# ram.net
KiCad netlist of a schematic drawn in EAGLE
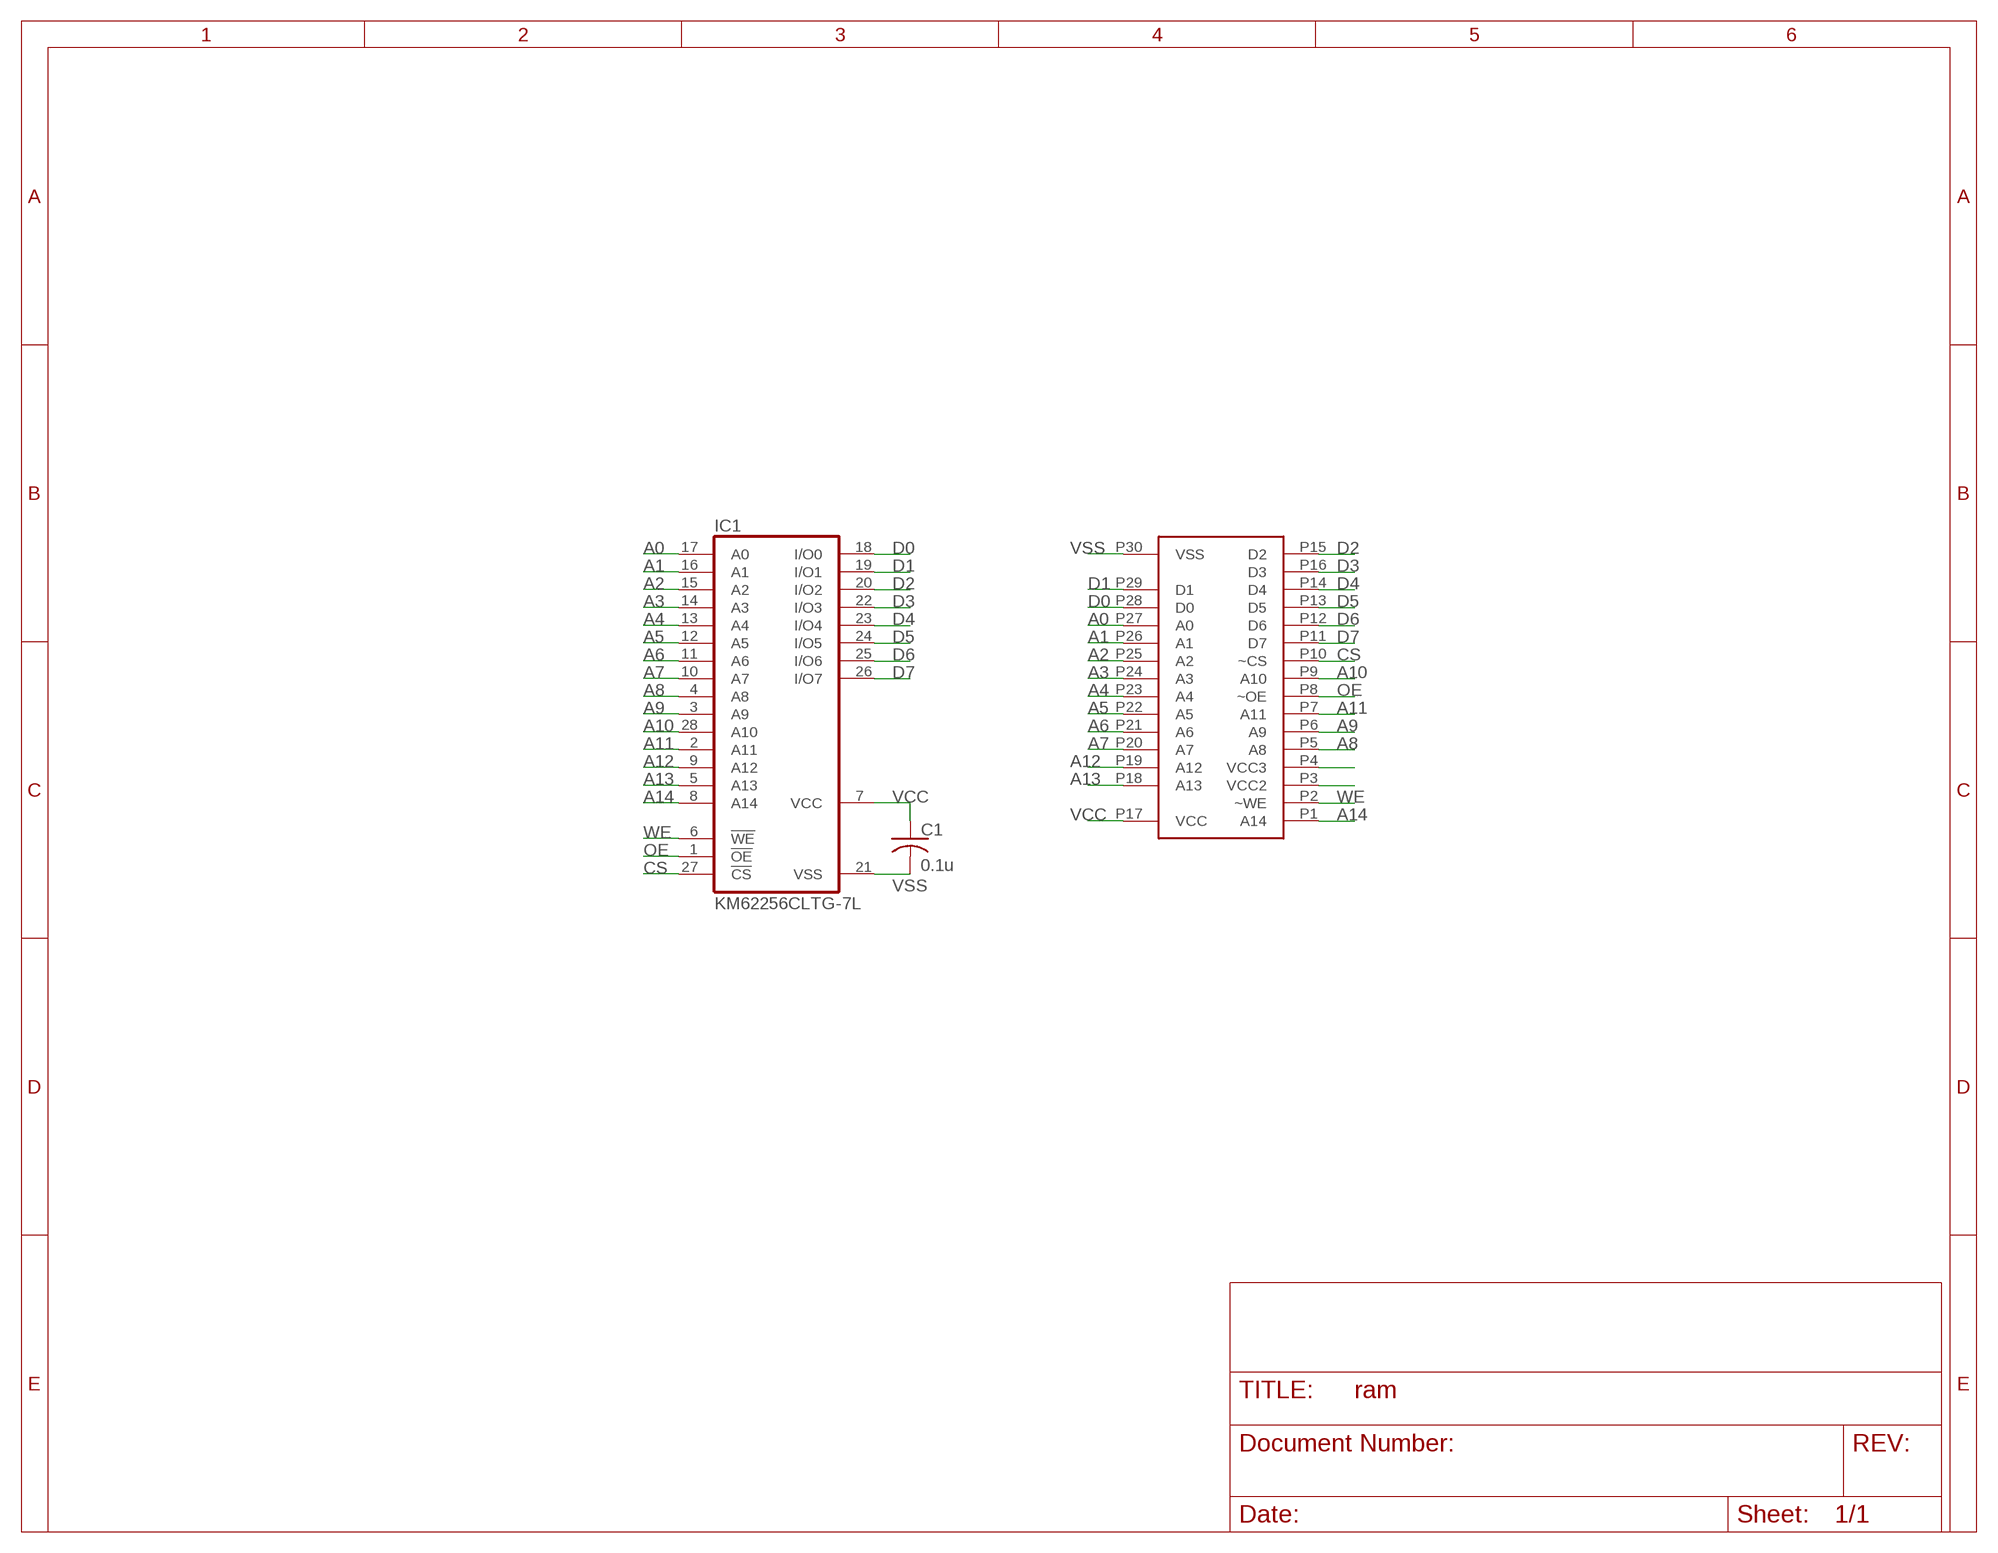
[diagram p0: schematic, sheet 1]

(export (version "E")
  (design (tool "Eeschema 10.0.6"))
  (components
    (comp (ref "C1")
      (value "0.1u")
      (footprint "eagle-import:C0603")
      (libsource (lib "eagle-import") (part "C-USC0603"))
    )
    (comp (ref "IC1")
      (value "KM62256CLTG-7L")
      (footprint "eagle-import:TSOP1-28")
      (libsource (lib "eagle-import") (part "KM62256C_TSOP28FLTG-7L"))
    )
    (comp (ref "U$1")
      (value "RAMPORT")
      (footprint "eagle-import:CASIORAM")
      (libsource (lib "eagle-import") (part "RAMPORT"))
    )
  )
  (nets
    (net (code "1") (name "/A0") (class "Default")
      (node (ref "IC1") (pin "17") (pinfunction "A0_17") (pintype "input"))
      (node (ref "U$1") (pin "P27") (pinfunction "A0_P27") (pintype "bidirectional"))
    )
    (net (code "2") (name "/A1") (class "Default")
      (node (ref "IC1") (pin "16") (pinfunction "A1_16") (pintype "input"))
      (node (ref "U$1") (pin "P26") (pinfunction "A1_P26") (pintype "bidirectional"))
    )
    (net (code "3") (name "/A2") (class "Default")
      (node (ref "IC1") (pin "15") (pinfunction "A2_15") (pintype "input"))
      (node (ref "U$1") (pin "P25") (pinfunction "A2_P25") (pintype "bidirectional"))
    )
    (net (code "4") (name "/A3") (class "Default")
      (node (ref "IC1") (pin "14") (pinfunction "A3_14") (pintype "input"))
      (node (ref "U$1") (pin "P24") (pinfunction "A3_P24") (pintype "bidirectional"))
    )
    (net (code "5") (name "/A4") (class "Default")
      (node (ref "IC1") (pin "13") (pinfunction "A4_13") (pintype "input"))
      (node (ref "U$1") (pin "P23") (pinfunction "A4_P23") (pintype "bidirectional"))
    )
    (net (code "6") (name "/A5") (class "Default")
      (node (ref "IC1") (pin "12") (pinfunction "A5_12") (pintype "input"))
      (node (ref "U$1") (pin "P22") (pinfunction "A5_P22") (pintype "bidirectional"))
    )
    (net (code "7") (name "/A6") (class "Default")
      (node (ref "IC1") (pin "11") (pinfunction "A6_11") (pintype "input"))
      (node (ref "U$1") (pin "P21") (pinfunction "A6_P21") (pintype "bidirectional"))
    )
    (net (code "8") (name "/A7") (class "Default")
      (node (ref "IC1") (pin "10") (pinfunction "A7_10") (pintype "input"))
      (node (ref "U$1") (pin "P20") (pinfunction "A7_P20") (pintype "bidirectional"))
    )
    (net (code "9") (name "/A8") (class "Default")
      (node (ref "IC1") (pin "4") (pinfunction "A8_4") (pintype "input"))
      (node (ref "U$1") (pin "P5") (pinfunction "A8_P5") (pintype "bidirectional"))
    )
    (net (code "10") (name "/A9") (class "Default")
      (node (ref "IC1") (pin "3") (pinfunction "A9_3") (pintype "input"))
      (node (ref "U$1") (pin "P6") (pinfunction "A9_P6") (pintype "bidirectional"))
    )
    (net (code "11") (name "/A10") (class "Default")
      (node (ref "IC1") (pin "28") (pinfunction "A10_28") (pintype "input"))
      (node (ref "U$1") (pin "P9") (pinfunction "A10_P9") (pintype "bidirectional"))
    )
    (net (code "12") (name "/A11") (class "Default")
      (node (ref "IC1") (pin "2") (pinfunction "A11_2") (pintype "input"))
      (node (ref "U$1") (pin "P7") (pinfunction "A11_P7") (pintype "bidirectional"))
    )
    (net (code "13") (name "/A12") (class "Default")
      (node (ref "IC1") (pin "9") (pinfunction "A12_9") (pintype "input"))
      (node (ref "U$1") (pin "P19") (pinfunction "A12_P19") (pintype "bidirectional"))
    )
    (net (code "14") (name "/A13") (class "Default")
      (node (ref "IC1") (pin "5") (pinfunction "A13_5") (pintype "input"))
      (node (ref "U$1") (pin "P18") (pinfunction "A13_P18") (pintype "bidirectional"))
    )
    (net (code "15") (name "/A14") (class "Default")
      (node (ref "IC1") (pin "8") (pinfunction "A14_8") (pintype "input"))
      (node (ref "U$1") (pin "P1") (pinfunction "A14_P1") (pintype "bidirectional"))
    )
    (net (code "16") (name "/CS") (class "Default")
      (node (ref "IC1") (pin "27") (pinfunction "~{CS}_27") (pintype "input"))
      (node (ref "U$1") (pin "P10") (pinfunction "~{CS}_P10") (pintype "bidirectional"))
    )
    (net (code "17") (name "/D0") (class "Default")
      (node (ref "IC1") (pin "18") (pinfunction "I/O0_18") (pintype "bidirectional"))
      (node (ref "U$1") (pin "P28") (pinfunction "D0_P28") (pintype "bidirectional"))
    )
    (net (code "18") (name "/D1") (class "Default")
      (node (ref "IC1") (pin "19") (pinfunction "I/O1_19") (pintype "bidirectional"))
      (node (ref "U$1") (pin "P29") (pinfunction "D1_P29") (pintype "bidirectional"))
    )
    (net (code "19") (name "/D2") (class "Default")
      (node (ref "IC1") (pin "20") (pinfunction "I/O2_20") (pintype "bidirectional"))
      (node (ref "U$1") (pin "P15") (pinfunction "D2_P15") (pintype "bidirectional"))
    )
    (net (code "20") (name "/D3") (class "Default")
      (node (ref "IC1") (pin "22") (pinfunction "I/O3_22") (pintype "bidirectional"))
      (node (ref "U$1") (pin "P16") (pinfunction "D3_P16") (pintype "bidirectional"))
    )
    (net (code "21") (name "/D4") (class "Default")
      (node (ref "IC1") (pin "23") (pinfunction "I/O4_23") (pintype "bidirectional"))
      (node (ref "U$1") (pin "P14") (pinfunction "D4_P14") (pintype "bidirectional"))
    )
    (net (code "22") (name "/D5") (class "Default")
      (node (ref "IC1") (pin "24") (pinfunction "I/O5_24") (pintype "bidirectional"))
      (node (ref "U$1") (pin "P13") (pinfunction "D5_P13") (pintype "bidirectional"))
    )
    (net (code "23") (name "/D6") (class "Default")
      (node (ref "IC1") (pin "25") (pinfunction "I/O6_25") (pintype "bidirectional"))
      (node (ref "U$1") (pin "P12") (pinfunction "D6_P12") (pintype "bidirectional"))
    )
    (net (code "24") (name "/D7") (class "Default")
      (node (ref "IC1") (pin "26") (pinfunction "I/O7_26") (pintype "bidirectional"))
      (node (ref "U$1") (pin "P11") (pinfunction "D7_P11") (pintype "bidirectional"))
    )
    (net (code "25") (name "/OE") (class "Default")
      (node (ref "IC1") (pin "1") (pinfunction "~{OE}_1") (pintype "input"))
      (node (ref "U$1") (pin "P8") (pinfunction "~{OE}_P8") (pintype "bidirectional"))
    )
    (net (code "26") (name "/VCC") (class "Default")
      (node (ref "C1") (pin "1") (pinfunction "1_1") (pintype "passive"))
      (node (ref "IC1") (pin "7") (pinfunction "VCC_7") (pintype "power_in"))
      (node (ref "U$1") (pin "P17") (pinfunction "VCC_P17") (pintype "bidirectional"))
    )
    (net (code "27") (name "/VSS") (class "Default")
      (node (ref "C1") (pin "2") (pinfunction "2_2") (pintype "passive"))
      (node (ref "IC1") (pin "21") (pinfunction "VSS_21") (pintype "power_in"))
      (node (ref "U$1") (pin "P30") (pinfunction "VSS_P30") (pintype "bidirectional"))
    )
    (net (code "28") (name "/WE") (class "Default")
      (node (ref "IC1") (pin "6") (pinfunction "~{WE}_6") (pintype "input"))
      (node (ref "U$1") (pin "P2") (pinfunction "~{WE}_P2") (pintype "bidirectional"))
    )
    (net (code "29") (name "unconnected-(U$1-VCC2-PadP3)") (class "Default")
      (node (ref "U$1") (pin "P3") (pinfunction "VCC2_P3") (pintype "bidirectional"))
    )
    (net (code "30") (name "unconnected-(U$1-VCC3-PadP4)") (class "Default")
      (node (ref "U$1") (pin "P4") (pinfunction "VCC3_P4") (pintype "bidirectional"))
    )
  )
)
